# macnano_power.net
KiCad netlist of a schematic drawn in EasyEDA Pro
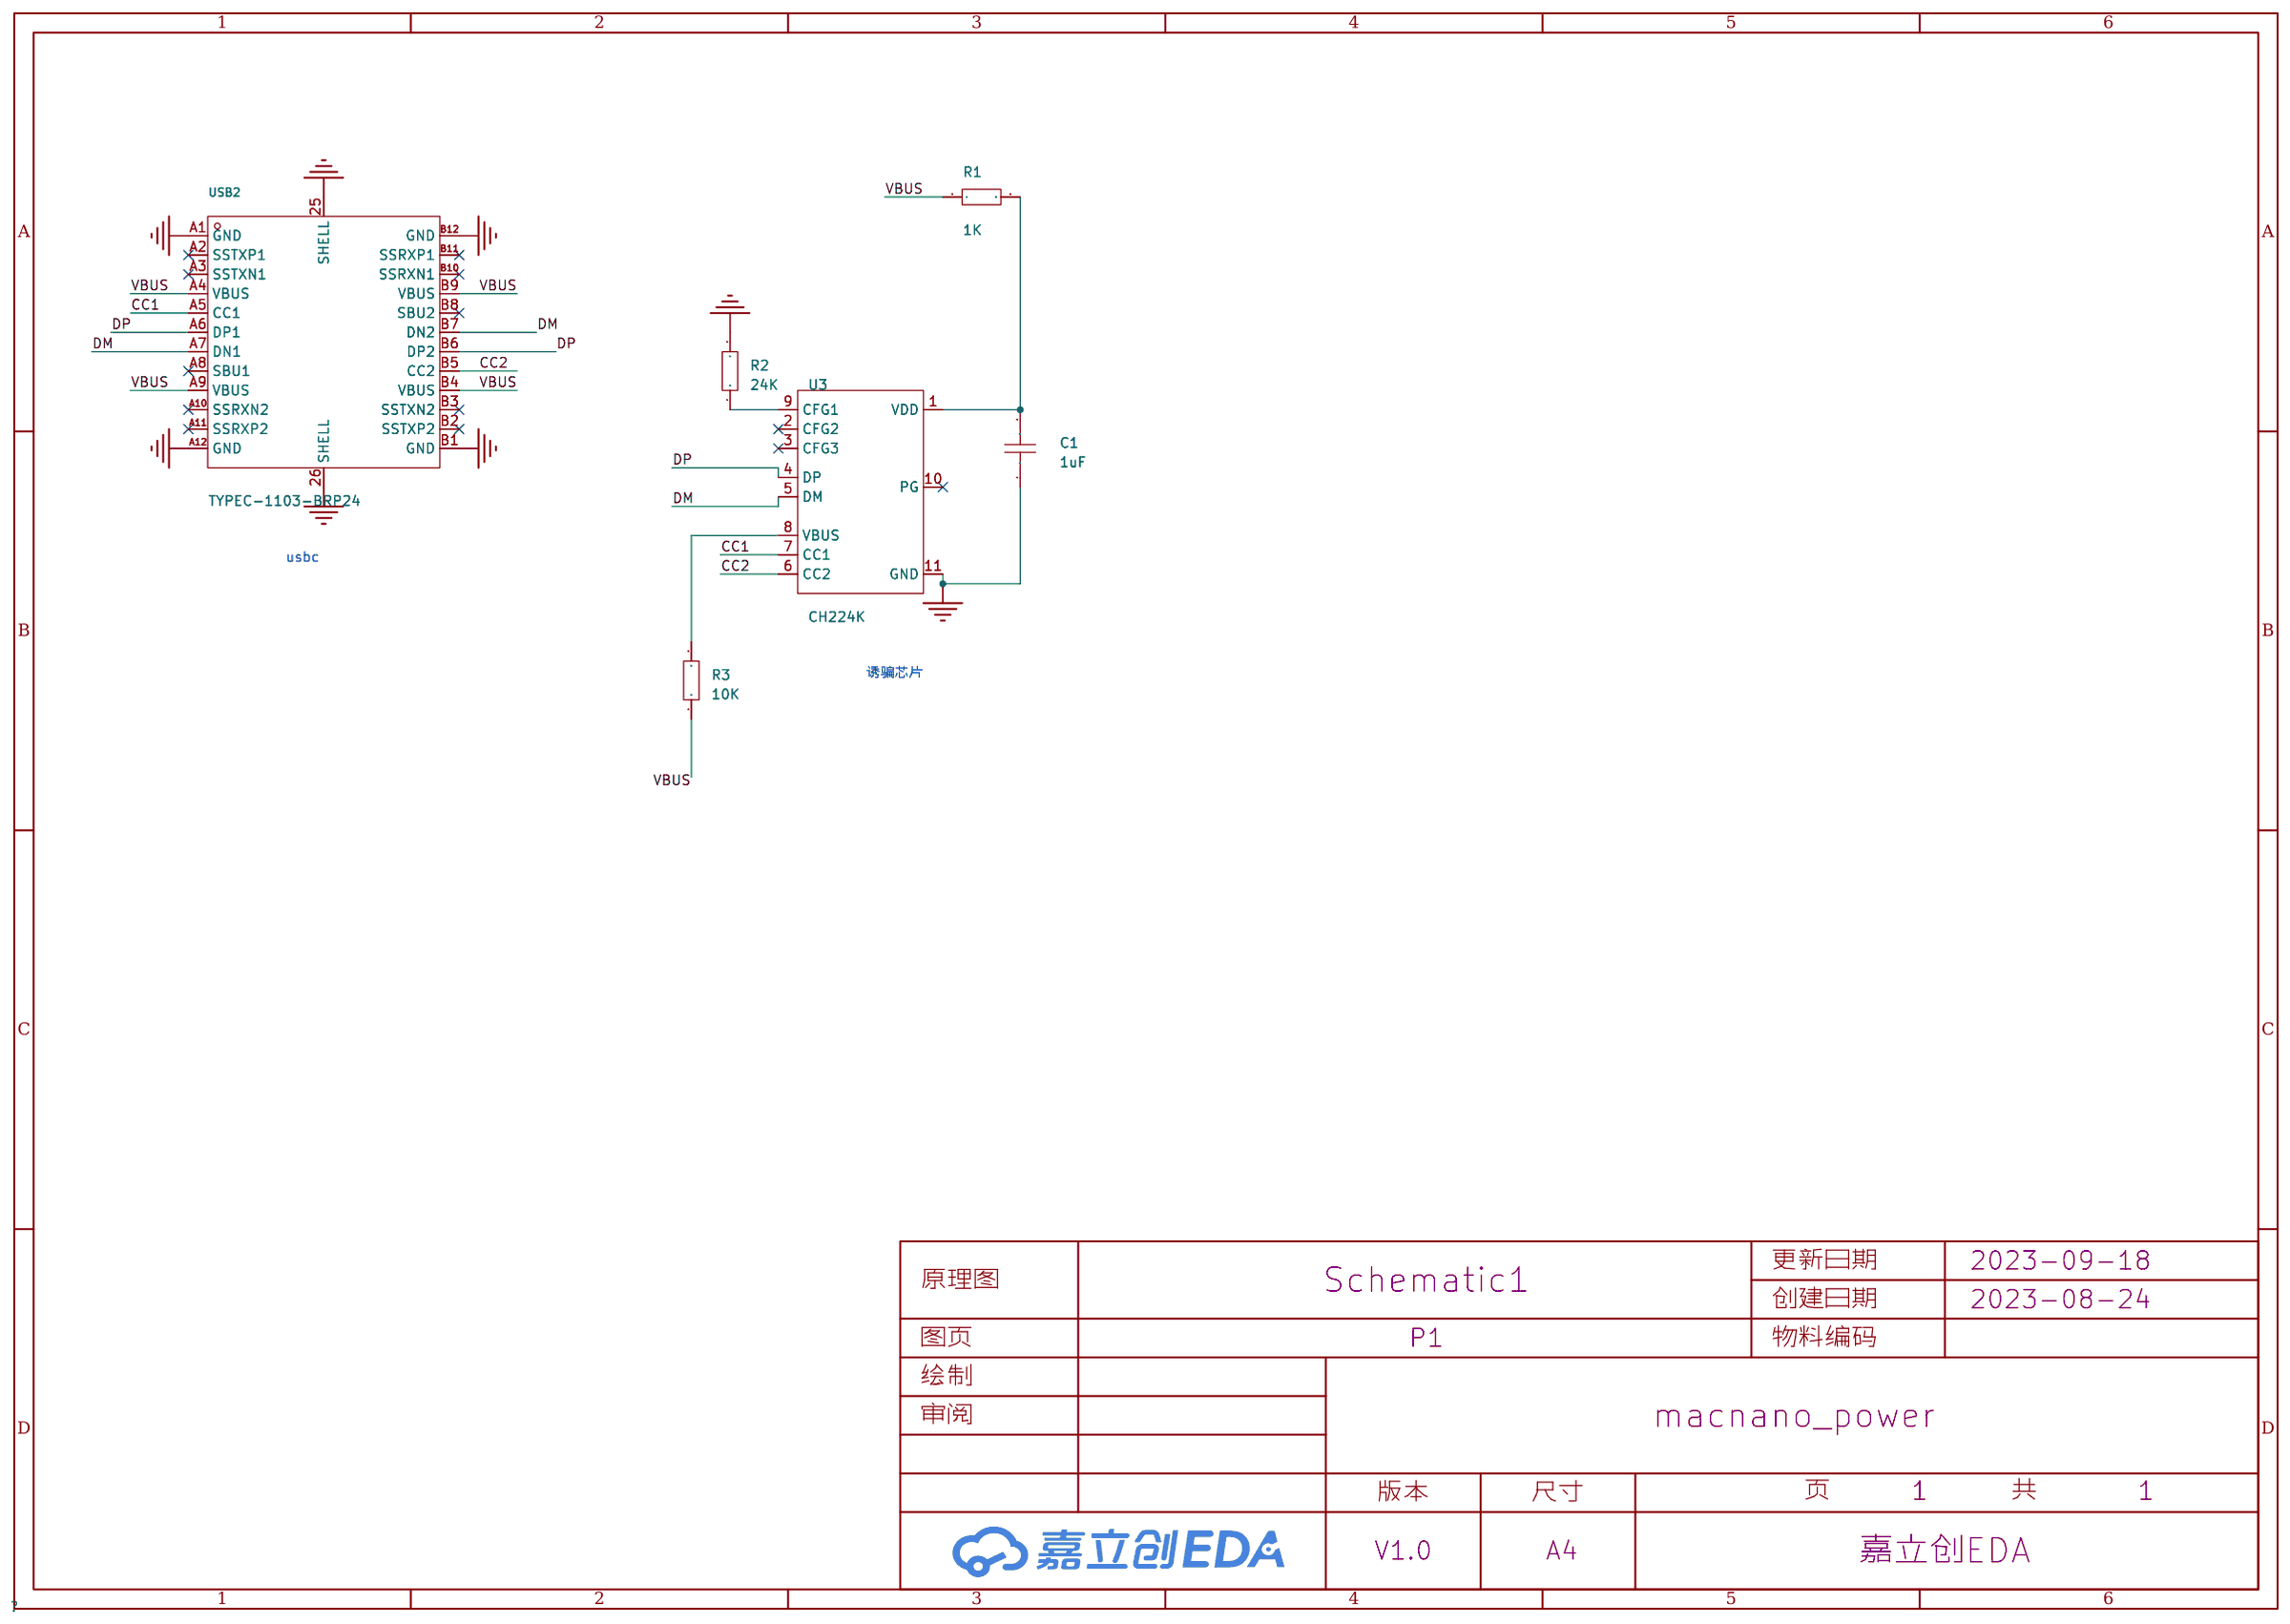
[diagram p0: schematic sheet]

(export (version "E")
  (design (tool "Eeschema 10.0.6"))
  (components
    (comp (ref "C1")
      (value "1uF")
      (footprint "easyedapro:C0603")
      (libsource (lib "easyedapro") (part "CapAcitance"))
    )
    (comp (ref "R1") (value "10K") (footprint "easyedapro:R0402") (libsource (lib "easyedapro") (part "电阻")))
    (comp (ref "R2") (value "24K") (footprint "easyedapro:R0402") (libsource (lib "easyedapro") (part "电阻")))
    (comp (ref "R3") (value "10K") (footprint "easyedapro:R0402") (libsource (lib "easyedapro") (part "电阻")))
    (comp (ref "U3")
      (value "CH224K")
      (footprint "easyedapro:ESSOP-10_L4.9-W3.9-P1.0-LS6.0-TL-EP")
      (fields (field (name "Manufacturer") "WCH(南京沁恒)"))
      (libsource (lib "easyedapro") (part "CH224K"))
    )
    (comp (ref "USB2")
      (value "TYPEC-1103-BRP24")
      (footprint "easyedapro:USB-C-SMD_TYPEC-1103-BRP24")
      (fields (field (name "Manufacturer") "XUNPU(讯普)"))
      (libsource (lib "easyedapro") (part "TYPEC-1103-BRP24"))
    )
  )
  (nets
    (net (code "1") (name "/CC1") (class "Default")
      (node (ref "U3") (pin "7") (pinfunction "CC1_7") (pintype "input"))
      (node (ref "USB2") (pin "A5") (pinfunction "CC1_A5") (pintype "input"))
    )
    (net (code "2") (name "/CC2") (class "Default")
      (node (ref "U3") (pin "6") (pinfunction "CC2_6") (pintype "input"))
      (node (ref "USB2") (pin "B5") (pinfunction "CC2_B5") (pintype "input"))
    )
    (net (code "3") (name "/DM") (class "Default")
      (node (ref "U3") (pin "5") (pinfunction "DM_5") (pintype "input"))
      (node (ref "USB2") (pin "A7") (pinfunction "DN1_A7") (pintype "input"))
      (node (ref "USB2") (pin "B7") (pinfunction "DN2_B7") (pintype "input"))
    )
    (net (code "4") (name "/DP") (class "Default")
      (node (ref "U3") (pin "4") (pinfunction "DP_4") (pintype "input"))
      (node (ref "USB2") (pin "A6") (pinfunction "DP1_A6") (pintype "input"))
      (node (ref "USB2") (pin "B6") (pinfunction "DP2_B6") (pintype "input"))
    )
    (net (code "5") (name "/VBUS") (class "Default")
      (node (ref "R1") (pin "1") (pinfunction "1_1") (pintype "input"))
      (node (ref "R3") (pin "1") (pinfunction "1_1") (pintype "input"))
      (node (ref "USB2") (pin "A4") (pinfunction "VBUS_A4") (pintype "input"))
      (node (ref "USB2") (pin "A9") (pinfunction "VBUS_A9") (pintype "input"))
      (node (ref "USB2") (pin "B4") (pinfunction "VBUS_B4") (pintype "input"))
      (node (ref "USB2") (pin "B9") (pinfunction "VBUS_B9") (pintype "input"))
    )
    (net (code "6") (name "GND") (class "Default")
      (node (ref "C1") (pin "1") (pinfunction "1_1") (pintype "input"))
      (node (ref "R2") (pin "2") (pinfunction "2_2") (pintype "input"))
      (node (ref "U3") (pin "11") (pinfunction "GND_11") (pintype "input"))
      (node (ref "USB2") (pin "25") (pinfunction "SHELL_25") (pintype "input"))
      (node (ref "USB2") (pin "26") (pinfunction "SHELL_26") (pintype "input"))
      (node (ref "USB2") (pin "A1") (pinfunction "GND_A1") (pintype "input"))
      (node (ref "USB2") (pin "A12") (pinfunction "GND_A12") (pintype "input"))
      (node (ref "USB2") (pin "B1") (pinfunction "GND_B1") (pintype "input"))
      (node (ref "USB2") (pin "B12") (pinfunction "GND_B12") (pintype "input"))
    )
    (net (code "7") (name "Net-(U3-CFG1)") (class "Default")
      (node (ref "R2") (pin "1") (pinfunction "1_1") (pintype "input"))
      (node (ref "U3") (pin "9") (pinfunction "CFG1_9") (pintype "input"))
    )
    (net (code "8") (name "Net-(U3-VBUS)") (class "Default")
      (node (ref "R3") (pin "2") (pinfunction "2_2") (pintype "input"))
      (node (ref "U3") (pin "8") (pinfunction "VBUS_8") (pintype "input"))
    )
    (net (code "9") (name "Net-(U3-VDD)") (class "Default")
      (node (ref "C1") (pin "2") (pinfunction "2_2") (pintype "input"))
      (node (ref "R1") (pin "2") (pinfunction "2_2") (pintype "input"))
      (node (ref "U3") (pin "1") (pinfunction "VDD_1") (pintype "input"))
    )
    (net (code "10") (name "unconnected-(U3-CFG2-Pad2)") (class "Default")
      (node (ref "U3") (pin "2") (pinfunction "CFG2_2") (pintype "input+no_connect"))
    )
    (net (code "11") (name "unconnected-(U3-CFG3-Pad3)") (class "Default")
      (node (ref "U3") (pin "3") (pinfunction "CFG3_3") (pintype "input+no_connect"))
    )
    (net (code "12") (name "unconnected-(U3-PG-Pad10)") (class "Default")
      (node (ref "U3") (pin "10") (pinfunction "PG_10") (pintype "input+no_connect"))
    )
    (net (code "13") (name "unconnected-(USB2-SBU1-PadA8)") (class "Default")
      (node (ref "USB2") (pin "A8") (pinfunction "SBU1_A8") (pintype "input+no_connect"))
    )
    (net (code "14") (name "unconnected-(USB2-SBU2-PadB8)") (class "Default")
      (node (ref "USB2") (pin "B8") (pinfunction "SBU2_B8") (pintype "input+no_connect"))
    )
    (net (code "15") (name "unconnected-(USB2-SSRXN1-PadB10)") (class "Default")
      (node (ref "USB2") (pin "B10") (pinfunction "SSRXN1_B10") (pintype "input+no_connect"))
    )
    (net (code "16") (name "unconnected-(USB2-SSRXN2-PadA10)") (class "Default")
      (node (ref "USB2") (pin "A10") (pinfunction "SSRXN2_A10") (pintype "input+no_connect"))
    )
    (net (code "17") (name "unconnected-(USB2-SSRXP1-PadB11)") (class "Default")
      (node (ref "USB2") (pin "B11") (pinfunction "SSRXP1_B11") (pintype "input+no_connect"))
    )
    (net (code "18") (name "unconnected-(USB2-SSRXP2-PadA11)") (class "Default")
      (node (ref "USB2") (pin "A11") (pinfunction "SSRXP2_A11") (pintype "input+no_connect"))
    )
    (net (code "19") (name "unconnected-(USB2-SSTXN1-PadA3)") (class "Default")
      (node (ref "USB2") (pin "A3") (pinfunction "SSTXN1_A3") (pintype "input+no_connect"))
    )
    (net (code "20") (name "unconnected-(USB2-SSTXN2-PadB3)") (class "Default")
      (node (ref "USB2") (pin "B3") (pinfunction "SSTXN2_B3") (pintype "input+no_connect"))
    )
    (net (code "21") (name "unconnected-(USB2-SSTXP1-PadA2)") (class "Default")
      (node (ref "USB2") (pin "A2") (pinfunction "SSTXP1_A2") (pintype "input+no_connect"))
    )
    (net (code "22") (name "unconnected-(USB2-SSTXP2-PadB2)") (class "Default")
      (node (ref "USB2") (pin "B2") (pinfunction "SSTXP2_B2") (pintype "input+no_connect"))
    )
  )
)
